# MotionSensorBoard.net
KiCad netlist of a schematic drawn in EAGLE
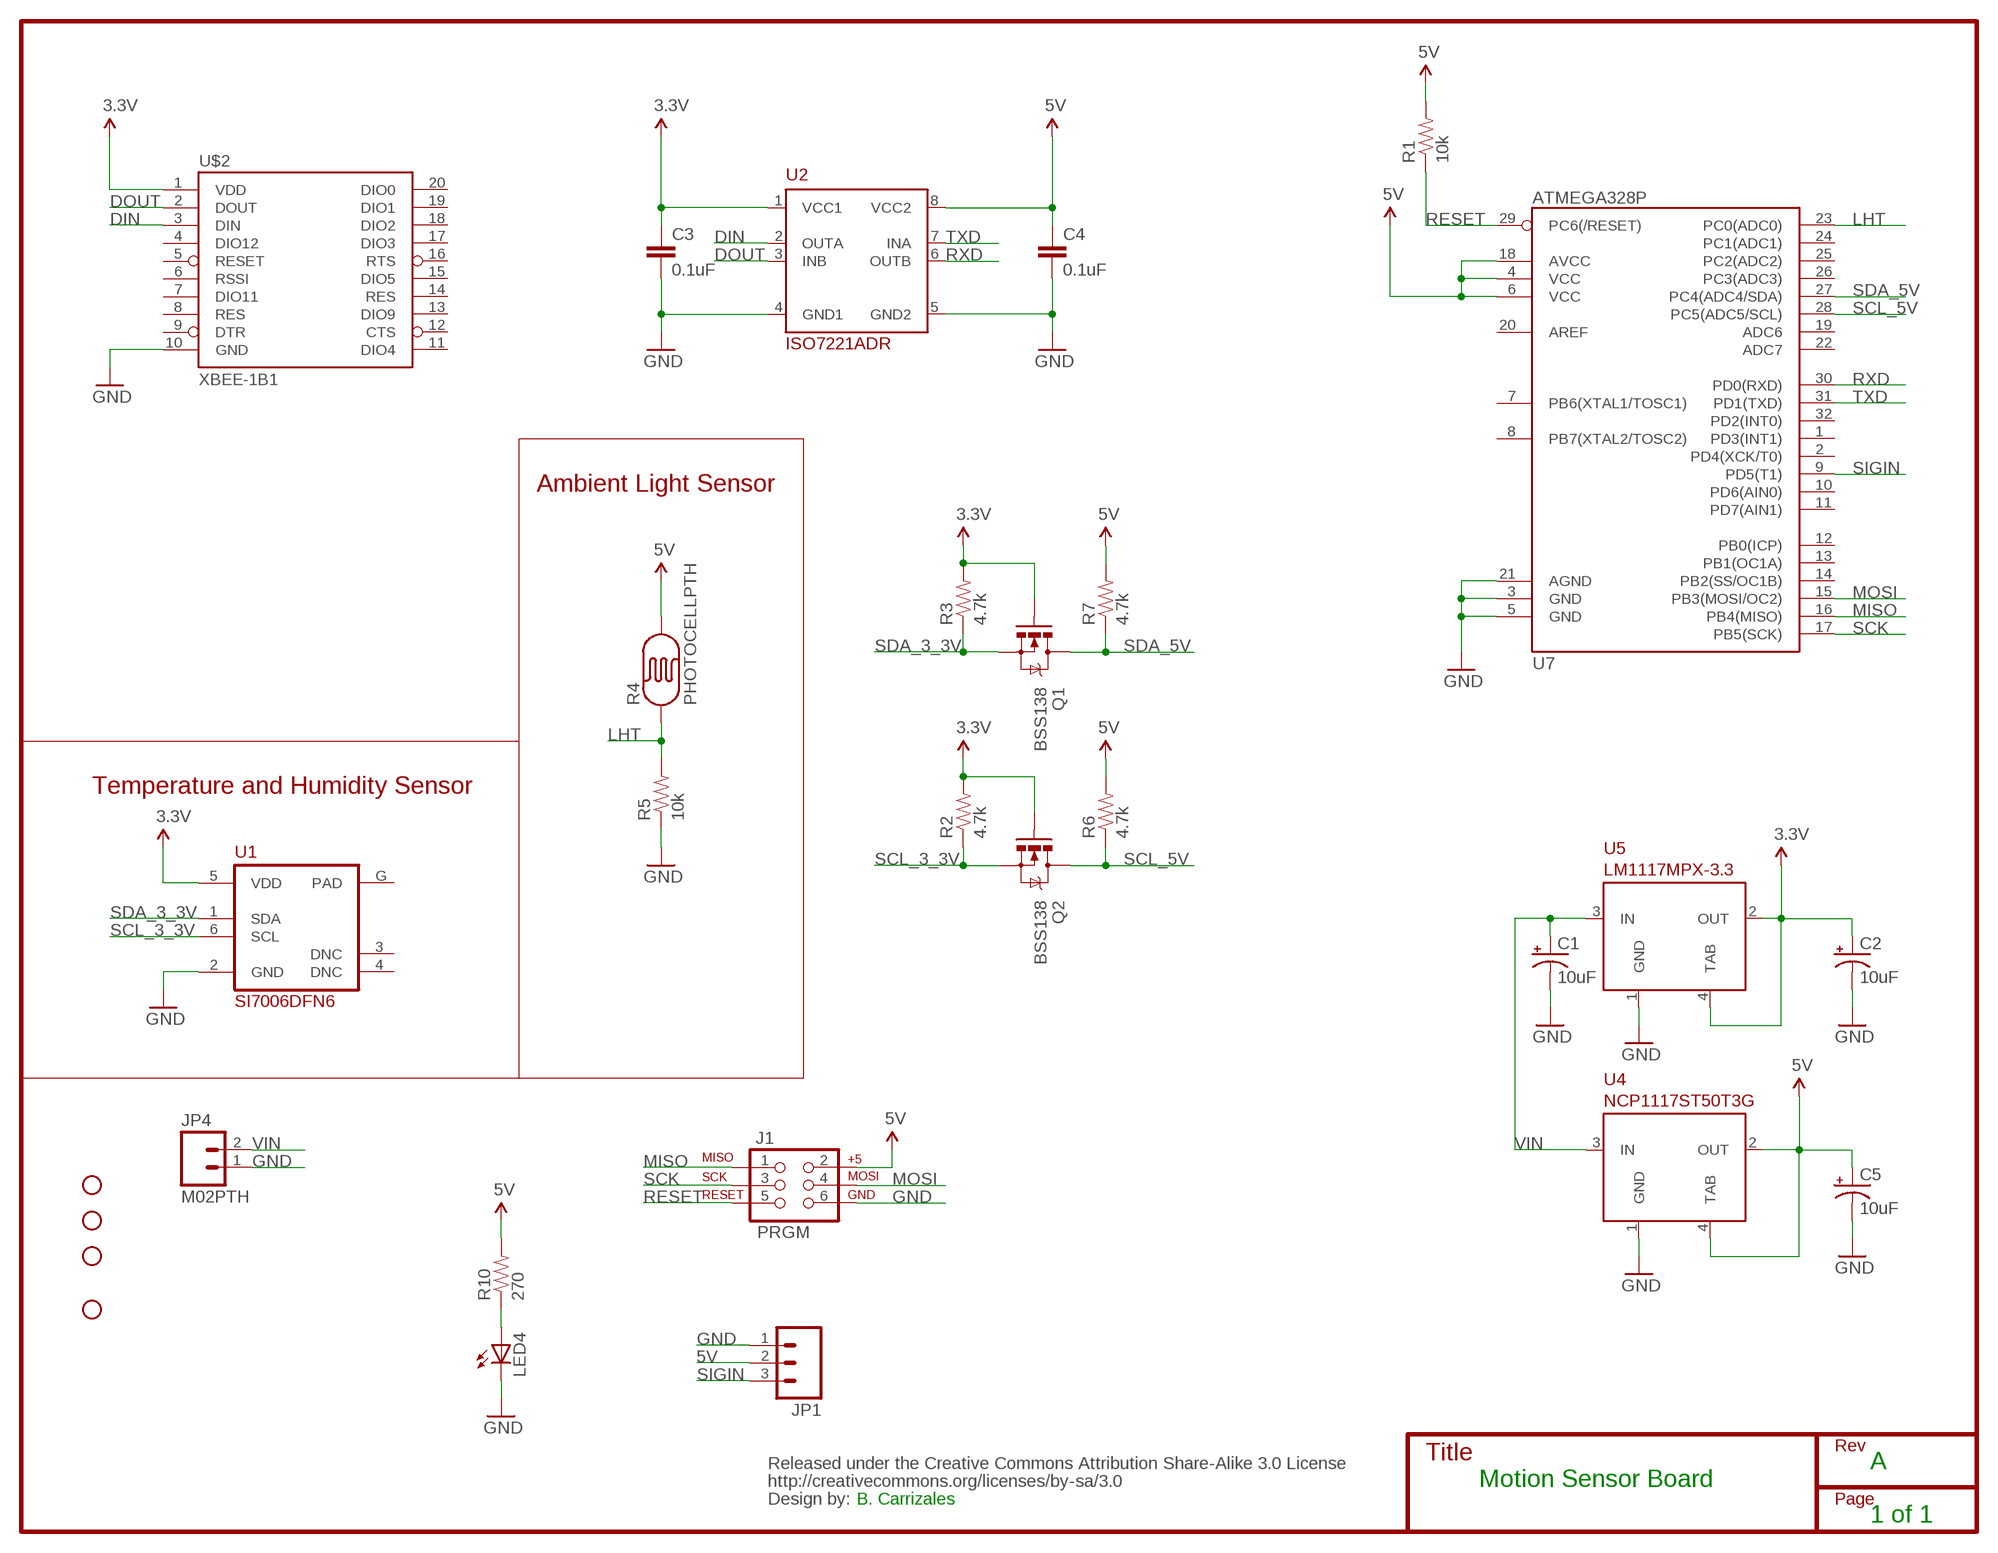
[diagram p0: schematic, sheet 1]

(export (version "E")
  (design (tool "Eeschema 10.0.6"))
  (components
    (comp (ref "C1")
      (value "10uF")
      (footprint "eagle-import:EIA6032")
      (libsource (lib "eagle-import") (part "CAP_POL6032"))
    )
    (comp (ref "C2")
      (value "10uF")
      (footprint "eagle-import:EIA6032")
      (libsource (lib "eagle-import") (part "CAP_POL6032"))
    )
    (comp (ref "C3")
      (value "0.1uF")
      (footprint "eagle-import:0603-CAP")
      (libsource (lib "eagle-import") (part "CAP0603-CAP"))
    )
    (comp (ref "C4")
      (value "0.1uF")
      (footprint "eagle-import:0603-CAP")
      (libsource (lib "eagle-import") (part "CAP0603-CAP"))
    )
    (comp (ref "C5")
      (value "10uF")
      (footprint "eagle-import:EIA6032")
      (libsource (lib "eagle-import") (part "CAP_POL6032"))
    )
    (comp (ref "CC_TEXT1")
      (value "CREATIVE_COMMONS")
      (footprint "eagle-import:CREATIVE_COMMONS")
      (libsource (lib "eagle-import") (part "CREATIVE_COMMONS"))
    )
    (comp (ref "J1")
      (value "PRGM")
      (footprint "eagle-import:2X3")
      (libsource (lib "eagle-import") (part "AVR_SPI_PRG_6PTH"))
    )
    (comp (ref "JP1")
      (value "M03PTH")
      (footprint "eagle-import:1X03")
      (libsource (lib "eagle-import") (part "M03PTH"))
    )
    (comp (ref "JP4")
      (value "M02PTH")
      (footprint "eagle-import:1X02")
      (libsource (lib "eagle-import") (part "M02PTH"))
    )
    (comp (ref "LED4")
      (value "LED0603")
      (footprint "eagle-import:LED-0603")
      (libsource (lib "eagle-import") (part "LED0603"))
    )
    (comp (ref "Q1")
      (value "BSS138")
      (footprint "eagle-import:SOT23")
      (libsource (lib "eagle-import") (part "MOSFET-NCHANNELBSS123LT1G"))
    )
    (comp (ref "Q2")
      (value "BSS138")
      (footprint "eagle-import:SOT23")
      (libsource (lib "eagle-import") (part "MOSFET-NCHANNELBSS123LT1G"))
    )
    (comp (ref "R1")
      (value "10k")
      (footprint "eagle-import:0603-RES")
      (libsource (lib "eagle-import") (part "RESISTOR0603-RES"))
    )
    (comp (ref "R2")
      (value "4.7k")
      (footprint "eagle-import:0603-RES")
      (libsource (lib "eagle-import") (part "RESISTOR0603"))
    )
    (comp (ref "R3")
      (value "4.7k")
      (footprint "eagle-import:0603-RES")
      (libsource (lib "eagle-import") (part "RESISTOR0603"))
    )
    (comp (ref "R4")
      (value "PHOTOCELLPTH")
      (footprint "eagle-import:PHOTOCELL")
      (libsource (lib "eagle-import") (part "PHOTOCELLPTH"))
    )
    (comp (ref "R5")
      (value "10k")
      (footprint "eagle-import:0603-RES")
      (libsource (lib "eagle-import") (part "RESISTOR0603"))
    )
    (comp (ref "R6")
      (value "4.7k")
      (footprint "eagle-import:0603-RES")
      (libsource (lib "eagle-import") (part "RESISTOR0603"))
    )
    (comp (ref "R7")
      (value "4.7k")
      (footprint "eagle-import:0603-RES")
      (libsource (lib "eagle-import") (part "RESISTOR0603"))
    )
    (comp (ref "R10")
      (value "270")
      (footprint "eagle-import:0603-RES")
      (libsource (lib "eagle-import") (part "RESISTOR0603-RES"))
    )
    (comp (ref "STANDOFF1")
      (value "STAND-OFF")
      (footprint "eagle-import:STAND-OFF")
      (libsource (lib "eagle-import") (part "STAND-OFF"))
    )
    (comp (ref "STANDOFF2")
      (value "STAND-OFF")
      (footprint "eagle-import:STAND-OFF")
      (libsource (lib "eagle-import") (part "STAND-OFF"))
    )
    (comp (ref "STANDOFF3")
      (value "STAND-OFF")
      (footprint "eagle-import:STAND-OFF")
      (libsource (lib "eagle-import") (part "STAND-OFF"))
    )
    (comp (ref "STANDOFF4")
      (value "STAND-OFF")
      (footprint "eagle-import:STAND-OFF")
      (libsource (lib "eagle-import") (part "STAND-OFF"))
    )
    (comp (ref "U$2")
      (value "XBEE-1B1")
      (footprint "eagle-import:XBEE-1")
      (libsource (lib "eagle-import") (part "XBEE-1B1"))
    )
    (comp (ref "U1")
      (value "SI7006DFN6")
      (footprint "eagle-import:DFN-6")
      (libsource (lib "eagle-import") (part "SI7006DFN6"))
    )
    (comp (ref "U2")
      (value "ISO7221ADR")
      (footprint "eagle-import:SO08")
      (fields (field (name "DIGIKEYPART#") "296-21955-1-ND"))
      (libsource (lib "eagle-import") (part "ISO7221ADR"))
    )
    (comp (ref "U4")
      (value "NCP1117ST50T3G")
      (footprint "eagle-import:SOT223")
      (fields (field (name "DIGIKEYPART#") "NCP1117ST50T3GOSCT-ND"))
      (libsource (lib "eagle-import") (part "NCP1117ST50T3G"))
    )
    (comp (ref "U5")
      (value "LM1117MPX-3.3")
      (footprint "eagle-import:SOT223")
      (fields (field (name "DIGIKEYPART#") "LM1117MPX-3.3/NOPBCT-ND"))
      (libsource (lib "eagle-import") (part "LM1117MPX-3.3"))
    )
    (comp (ref "U7")
      (value "ATMEGA328P")
      (footprint "eagle-import:TQFP32-08")
      (libsource (lib "eagle-import") (part "ATMEGA328_SMT"))
    )
  )
  (nets
    (net (code "1") (name "/DIN") (class "Default")
      (node (ref "U$2") (pin "3") (pinfunction "DIN_3") (pintype "input"))
      (node (ref "U2") (pin "2") (pinfunction "OUTA_2") (pintype "bidirectional"))
    )
    (net (code "2") (name "/DOUT") (class "Default")
      (node (ref "U$2") (pin "2") (pinfunction "DOUT_2") (pintype "output"))
      (node (ref "U2") (pin "3") (pinfunction "INB_3") (pintype "bidirectional"))
    )
    (net (code "3") (name "/LHT") (class "Default")
      (node (ref "R4") (pin "1") (pinfunction "P$1_1") (pintype "bidirectional"))
      (node (ref "R5") (pin "2") (pinfunction "2_2") (pintype "passive"))
      (node (ref "U7") (pin "23") (pinfunction "PC0(ADC0)_23") (pintype "bidirectional"))
    )
    (net (code "4") (name "/MISO") (class "Default")
      (node (ref "J1") (pin "1") (pinfunction "1_1") (pintype "passive"))
      (node (ref "U7") (pin "16") (pinfunction "PB4(MISO)_16") (pintype "bidirectional"))
    )
    (net (code "5") (name "/MOSI") (class "Default")
      (node (ref "J1") (pin "4") (pinfunction "4_4") (pintype "passive"))
      (node (ref "U7") (pin "15") (pinfunction "PB3(MOSI/OC2)_15") (pintype "bidirectional"))
    )
    (net (code "6") (name "/RESET") (class "Default")
      (node (ref "J1") (pin "5") (pinfunction "5_5") (pintype "passive"))
      (node (ref "R1") (pin "1") (pinfunction "1_1") (pintype "passive"))
      (node (ref "U7") (pin "29") (pinfunction "PC6(/RESET)_29") (pintype "bidirectional"))
    )
    (net (code "7") (name "/RXD") (class "Default")
      (node (ref "U2") (pin "6") (pinfunction "OUTB_6") (pintype "bidirectional"))
      (node (ref "U7") (pin "30") (pinfunction "PD0(RXD)_30") (pintype "bidirectional"))
    )
    (net (code "8") (name "/SCK") (class "Default")
      (node (ref "J1") (pin "3") (pinfunction "3_3") (pintype "passive"))
      (node (ref "U7") (pin "17") (pinfunction "PB5(SCK)_17") (pintype "bidirectional"))
    )
    (net (code "9") (name "/SCL_3_3V") (class "Default")
      (node (ref "Q2") (pin "2") (pinfunction "S_2") (pintype "passive"))
      (node (ref "R2") (pin "1") (pinfunction "1_1") (pintype "passive"))
      (node (ref "U1") (pin "6") (pinfunction "SCL_6") (pintype "bidirectional"))
    )
    (net (code "10") (name "/SCL_5V") (class "Default")
      (node (ref "Q2") (pin "3") (pinfunction "D_3") (pintype "passive"))
      (node (ref "R6") (pin "1") (pinfunction "1_1") (pintype "passive"))
      (node (ref "U7") (pin "28") (pinfunction "PC5(ADC5/SCL)_28") (pintype "bidirectional"))
    )
    (net (code "11") (name "/SDA_3_3V") (class "Default")
      (node (ref "Q1") (pin "2") (pinfunction "S_2") (pintype "passive"))
      (node (ref "R3") (pin "1") (pinfunction "1_1") (pintype "passive"))
      (node (ref "U1") (pin "1") (pinfunction "SDA_1") (pintype "bidirectional"))
    )
    (net (code "12") (name "/SDA_5V") (class "Default")
      (node (ref "Q1") (pin "3") (pinfunction "D_3") (pintype "passive"))
      (node (ref "R7") (pin "1") (pinfunction "1_1") (pintype "passive"))
      (node (ref "U7") (pin "27") (pinfunction "PC4(ADC4/SDA)_27") (pintype "bidirectional"))
    )
    (net (code "13") (name "/SIGIN") (class "Default")
      (node (ref "JP1") (pin "3") (pinfunction "3_3") (pintype "passive"))
      (node (ref "U7") (pin "9") (pinfunction "PD5(T1)_9") (pintype "bidirectional"))
    )
    (net (code "14") (name "/TXD") (class "Default")
      (node (ref "U2") (pin "7") (pinfunction "INA_7") (pintype "bidirectional"))
      (node (ref "U7") (pin "31") (pinfunction "PD1(TXD)_31") (pintype "bidirectional"))
    )
    (net (code "15") (name "/VIN") (class "Default")
      (node (ref "C1") (pin "P$1") (pinfunction "+_P$1") (pintype "passive"))
      (node (ref "JP4") (pin "2") (pinfunction "2_2") (pintype "passive"))
      (node (ref "U4") (pin "3") (pinfunction "IN_3") (pintype "bidirectional"))
      (node (ref "U5") (pin "3") (pinfunction "IN_3") (pintype "bidirectional"))
    )
    (net (code "16") (name "3.3V") (class "Default")
      (node (ref "C2") (pin "P$1") (pinfunction "+_P$1") (pintype "passive"))
      (node (ref "C3") (pin "1") (pinfunction "1_1") (pintype "passive"))
      (node (ref "Q1") (pin "1") (pinfunction "G_1") (pintype "passive"))
      (node (ref "Q2") (pin "1") (pinfunction "G_1") (pintype "passive"))
      (node (ref "R2") (pin "2") (pinfunction "2_2") (pintype "passive"))
      (node (ref "R3") (pin "2") (pinfunction "2_2") (pintype "passive"))
      (node (ref "U$2") (pin "1") (pinfunction "VDD_1") (pintype "power_in"))
      (node (ref "U1") (pin "5") (pinfunction "VDD_5") (pintype "bidirectional"))
      (node (ref "U2") (pin "1") (pinfunction "VCC1_1") (pintype "bidirectional"))
      (node (ref "U5") (pin "2") (pinfunction "OUT_2") (pintype "bidirectional"))
      (node (ref "U5") (pin "4") (pinfunction "TAB_4") (pintype "bidirectional"))
    )
    (net (code "17") (name "5V") (class "Default")
      (node (ref "C4") (pin "1") (pinfunction "1_1") (pintype "passive"))
      (node (ref "C5") (pin "P$1") (pinfunction "+_P$1") (pintype "passive"))
      (node (ref "J1") (pin "2") (pinfunction "2_2") (pintype "passive"))
      (node (ref "JP1") (pin "2") (pinfunction "2_2") (pintype "passive"))
      (node (ref "R1") (pin "2") (pinfunction "2_2") (pintype "passive"))
      (node (ref "R10") (pin "2") (pinfunction "2_2") (pintype "passive"))
      (node (ref "R4") (pin "2") (pinfunction "P$2_2") (pintype "bidirectional"))
      (node (ref "R6") (pin "2") (pinfunction "2_2") (pintype "passive"))
      (node (ref "R7") (pin "2") (pinfunction "2_2") (pintype "passive"))
      (node (ref "U2") (pin "8") (pinfunction "VCC2_8") (pintype "bidirectional"))
      (node (ref "U4") (pin "2") (pinfunction "OUT_2") (pintype "bidirectional"))
      (node (ref "U4") (pin "4") (pinfunction "TAB_4") (pintype "bidirectional"))
      (node (ref "U7") (pin "18") (pinfunction "AVCC_18") (pintype "bidirectional"))
      (node (ref "U7") (pin "4") (pinfunction "VCC_4") (pintype "bidirectional"))
      (node (ref "U7") (pin "6") (pinfunction "VCC_6") (pintype "bidirectional"))
    )
    (net (code "18") (name "GND") (class "Default")
      (node (ref "C1") (pin "P$2") (pinfunction "-_P$2") (pintype "passive"))
      (node (ref "C2") (pin "P$2") (pinfunction "-_P$2") (pintype "passive"))
      (node (ref "C3") (pin "2") (pinfunction "2_2") (pintype "passive"))
      (node (ref "C4") (pin "2") (pinfunction "2_2") (pintype "passive"))
      (node (ref "C5") (pin "P$2") (pinfunction "-_P$2") (pintype "passive"))
      (node (ref "J1") (pin "6") (pinfunction "6_6") (pintype "passive"))
      (node (ref "JP1") (pin "1") (pinfunction "1_1") (pintype "passive"))
      (node (ref "JP4") (pin "1") (pinfunction "1_1") (pintype "passive"))
      (node (ref "LED4") (pin "C") (pinfunction "C_C") (pintype "passive"))
      (node (ref "R5") (pin "1") (pinfunction "1_1") (pintype "passive"))
      (node (ref "U$2") (pin "10") (pinfunction "GND_10") (pintype "power_in"))
      (node (ref "U1") (pin "2") (pinfunction "GND_2") (pintype "bidirectional"))
      (node (ref "U2") (pin "4") (pinfunction "GND1_4") (pintype "bidirectional"))
      (node (ref "U2") (pin "5") (pinfunction "GND2_5") (pintype "bidirectional"))
      (node (ref "U4") (pin "1") (pinfunction "GND_1") (pintype "bidirectional"))
      (node (ref "U5") (pin "1") (pinfunction "GND_1") (pintype "bidirectional"))
      (node (ref "U7") (pin "21") (pinfunction "AGND_21") (pintype "bidirectional"))
      (node (ref "U7") (pin "3") (pinfunction "GND_3") (pintype "bidirectional"))
      (node (ref "U7") (pin "5") (pinfunction "GND_5") (pintype "bidirectional"))
    )
    (net (code "19") (name "Net-(LED4-PadA)") (class "Default")
      (node (ref "LED4") (pin "A") (pinfunction "A_A") (pintype "passive"))
      (node (ref "R10") (pin "1") (pinfunction "1_1") (pintype "passive"))
    )
    (net (code "20") (name "unconnected-(U$2-CTS-Pad12)") (class "Default")
      (node (ref "U$2") (pin "12") (pinfunction "CTS_12") (pintype "output"))
    )
    (net (code "21") (name "unconnected-(U$2-DIO0-Pad20)") (class "Default")
      (node (ref "U$2") (pin "20") (pinfunction "DIO0_20") (pintype "bidirectional"))
    )
    (net (code "22") (name "unconnected-(U$2-DIO1-Pad19)") (class "Default")
      (node (ref "U$2") (pin "19") (pinfunction "DIO1_19") (pintype "bidirectional"))
    )
    (net (code "23") (name "unconnected-(U$2-DIO2-Pad18)") (class "Default")
      (node (ref "U$2") (pin "18") (pinfunction "DIO2_18") (pintype "bidirectional"))
    )
    (net (code "24") (name "unconnected-(U$2-DIO3-Pad17)") (class "Default")
      (node (ref "U$2") (pin "17") (pinfunction "DIO3_17") (pintype "bidirectional"))
    )
    (net (code "25") (name "unconnected-(U$2-DIO4-Pad11)") (class "Default")
      (node (ref "U$2") (pin "11") (pinfunction "DIO4_11") (pintype "bidirectional"))
    )
    (net (code "26") (name "unconnected-(U$2-DIO5-Pad15)") (class "Default")
      (node (ref "U$2") (pin "15") (pinfunction "DIO5_15") (pintype "bidirectional"))
    )
    (net (code "27") (name "unconnected-(U$2-DIO9-Pad13)") (class "Default")
      (node (ref "U$2") (pin "13") (pinfunction "DIO9_13") (pintype "bidirectional"))
    )
    (net (code "28") (name "unconnected-(U$2-DIO11-Pad7)") (class "Default")
      (node (ref "U$2") (pin "7") (pinfunction "DIO11_7") (pintype "bidirectional"))
    )
    (net (code "29") (name "unconnected-(U$2-DIO12-Pad4)") (class "Default")
      (node (ref "U$2") (pin "4") (pinfunction "DIO12_4") (pintype "bidirectional"))
    )
    (net (code "30") (name "unconnected-(U$2-DTR-Pad9)") (class "Default")
      (node (ref "U$2") (pin "9") (pinfunction "DTR_9") (pintype "bidirectional"))
    )
    (net (code "31") (name "unconnected-(U$2-RES-Pad8)") (class "Default")
      (node (ref "U$2") (pin "8") (pinfunction "RES_8") (pintype "bidirectional"))
    )
    (net (code "32") (name "unconnected-(U$2-RES-Pad14)") (class "Default")
      (node (ref "U$2") (pin "14") (pinfunction "RES_14") (pintype "bidirectional"))
    )
    (net (code "33") (name "unconnected-(U$2-RESET-Pad5)") (class "Default")
      (node (ref "U$2") (pin "5") (pinfunction "RESET_5") (pintype "input"))
    )
    (net (code "34") (name "unconnected-(U$2-RSSI-Pad6)") (class "Default")
      (node (ref "U$2") (pin "6") (pinfunction "RSSI_6") (pintype "bidirectional"))
    )
    (net (code "35") (name "unconnected-(U$2-RTS-Pad16)") (class "Default")
      (node (ref "U$2") (pin "16") (pinfunction "RTS_16") (pintype "input"))
    )
    (net (code "36") (name "unconnected-(U1-DNC-Pad3)") (class "Default")
      (node (ref "U1") (pin "3") (pinfunction "DNC_3") (pintype "bidirectional"))
    )
    (net (code "37") (name "unconnected-(U1-DNC-Pad4)") (class "Default")
      (node (ref "U1") (pin "4") (pinfunction "DNC_4") (pintype "bidirectional"))
    )
    (net (code "38") (name "unconnected-(U1-PAD-PadG)") (class "Default")
      (node (ref "U1") (pin "G") (pinfunction "PAD_G") (pintype "bidirectional"))
    )
    (net (code "39") (name "unconnected-(U7-ADC6-Pad19)") (class "Default")
      (node (ref "U7") (pin "19") (pinfunction "ADC6_19") (pintype "bidirectional"))
    )
    (net (code "40") (name "unconnected-(U7-ADC7-Pad22)") (class "Default")
      (node (ref "U7") (pin "22") (pinfunction "ADC7_22") (pintype "bidirectional"))
    )
    (net (code "41") (name "unconnected-(U7-AREF-Pad20)") (class "Default")
      (node (ref "U7") (pin "20") (pinfunction "AREF_20") (pintype "bidirectional"))
    )
    (net (code "42") (name "unconnected-(U7-PB0(ICP)-Pad12)") (class "Default")
      (node (ref "U7") (pin "12") (pinfunction "PB0(ICP)_12") (pintype "bidirectional"))
    )
    (net (code "43") (name "unconnected-(U7-PB1(OC1A)-Pad13)") (class "Default")
      (node (ref "U7") (pin "13") (pinfunction "PB1(OC1A)_13") (pintype "bidirectional"))
    )
    (net (code "44") (name "unconnected-(U7-PB2(SS{slash}OC1B)-Pad14)") (class "Default")
      (node (ref "U7") (pin "14") (pinfunction "PB2(SS/OC1B)_14") (pintype "bidirectional"))
    )
    (net (code "45") (name "unconnected-(U7-PB6(XTAL1{slash}TOSC1)-Pad7)") (class "Default")
      (node (ref "U7") (pin "7") (pinfunction "PB6(XTAL1/TOSC1)_7") (pintype "bidirectional"))
    )
    (net (code "46") (name "unconnected-(U7-PB7(XTAL2{slash}TOSC2)-Pad8)") (class "Default")
      (node (ref "U7") (pin "8") (pinfunction "PB7(XTAL2/TOSC2)_8") (pintype "bidirectional"))
    )
    (net (code "47") (name "unconnected-(U7-PC1(ADC1)-Pad24)") (class "Default")
      (node (ref "U7") (pin "24") (pinfunction "PC1(ADC1)_24") (pintype "bidirectional"))
    )
    (net (code "48") (name "unconnected-(U7-PC2(ADC2)-Pad25)") (class "Default")
      (node (ref "U7") (pin "25") (pinfunction "PC2(ADC2)_25") (pintype "bidirectional"))
    )
    (net (code "49") (name "unconnected-(U7-PC3(ADC3)-Pad26)") (class "Default")
      (node (ref "U7") (pin "26") (pinfunction "PC3(ADC3)_26") (pintype "bidirectional"))
    )
    (net (code "50") (name "unconnected-(U7-PD2(INT0)-Pad32)") (class "Default")
      (node (ref "U7") (pin "32") (pinfunction "PD2(INT0)_32") (pintype "bidirectional"))
    )
    (net (code "51") (name "unconnected-(U7-PD3(INT1)-Pad1)") (class "Default")
      (node (ref "U7") (pin "1") (pinfunction "PD3(INT1)_1") (pintype "bidirectional"))
    )
    (net (code "52") (name "unconnected-(U7-PD4(XCK{slash}T0)-Pad2)") (class "Default")
      (node (ref "U7") (pin "2") (pinfunction "PD4(XCK/T0)_2") (pintype "bidirectional"))
    )
    (net (code "53") (name "unconnected-(U7-PD6(AIN0)-Pad10)") (class "Default")
      (node (ref "U7") (pin "10") (pinfunction "PD6(AIN0)_10") (pintype "bidirectional"))
    )
    (net (code "54") (name "unconnected-(U7-PD7(AIN1)-Pad11)") (class "Default")
      (node (ref "U7") (pin "11") (pinfunction "PD7(AIN1)_11") (pintype "bidirectional"))
    )
  )
)
